# satima_clone.net
KiCad netlist of a schematic drawn in EasyEDA
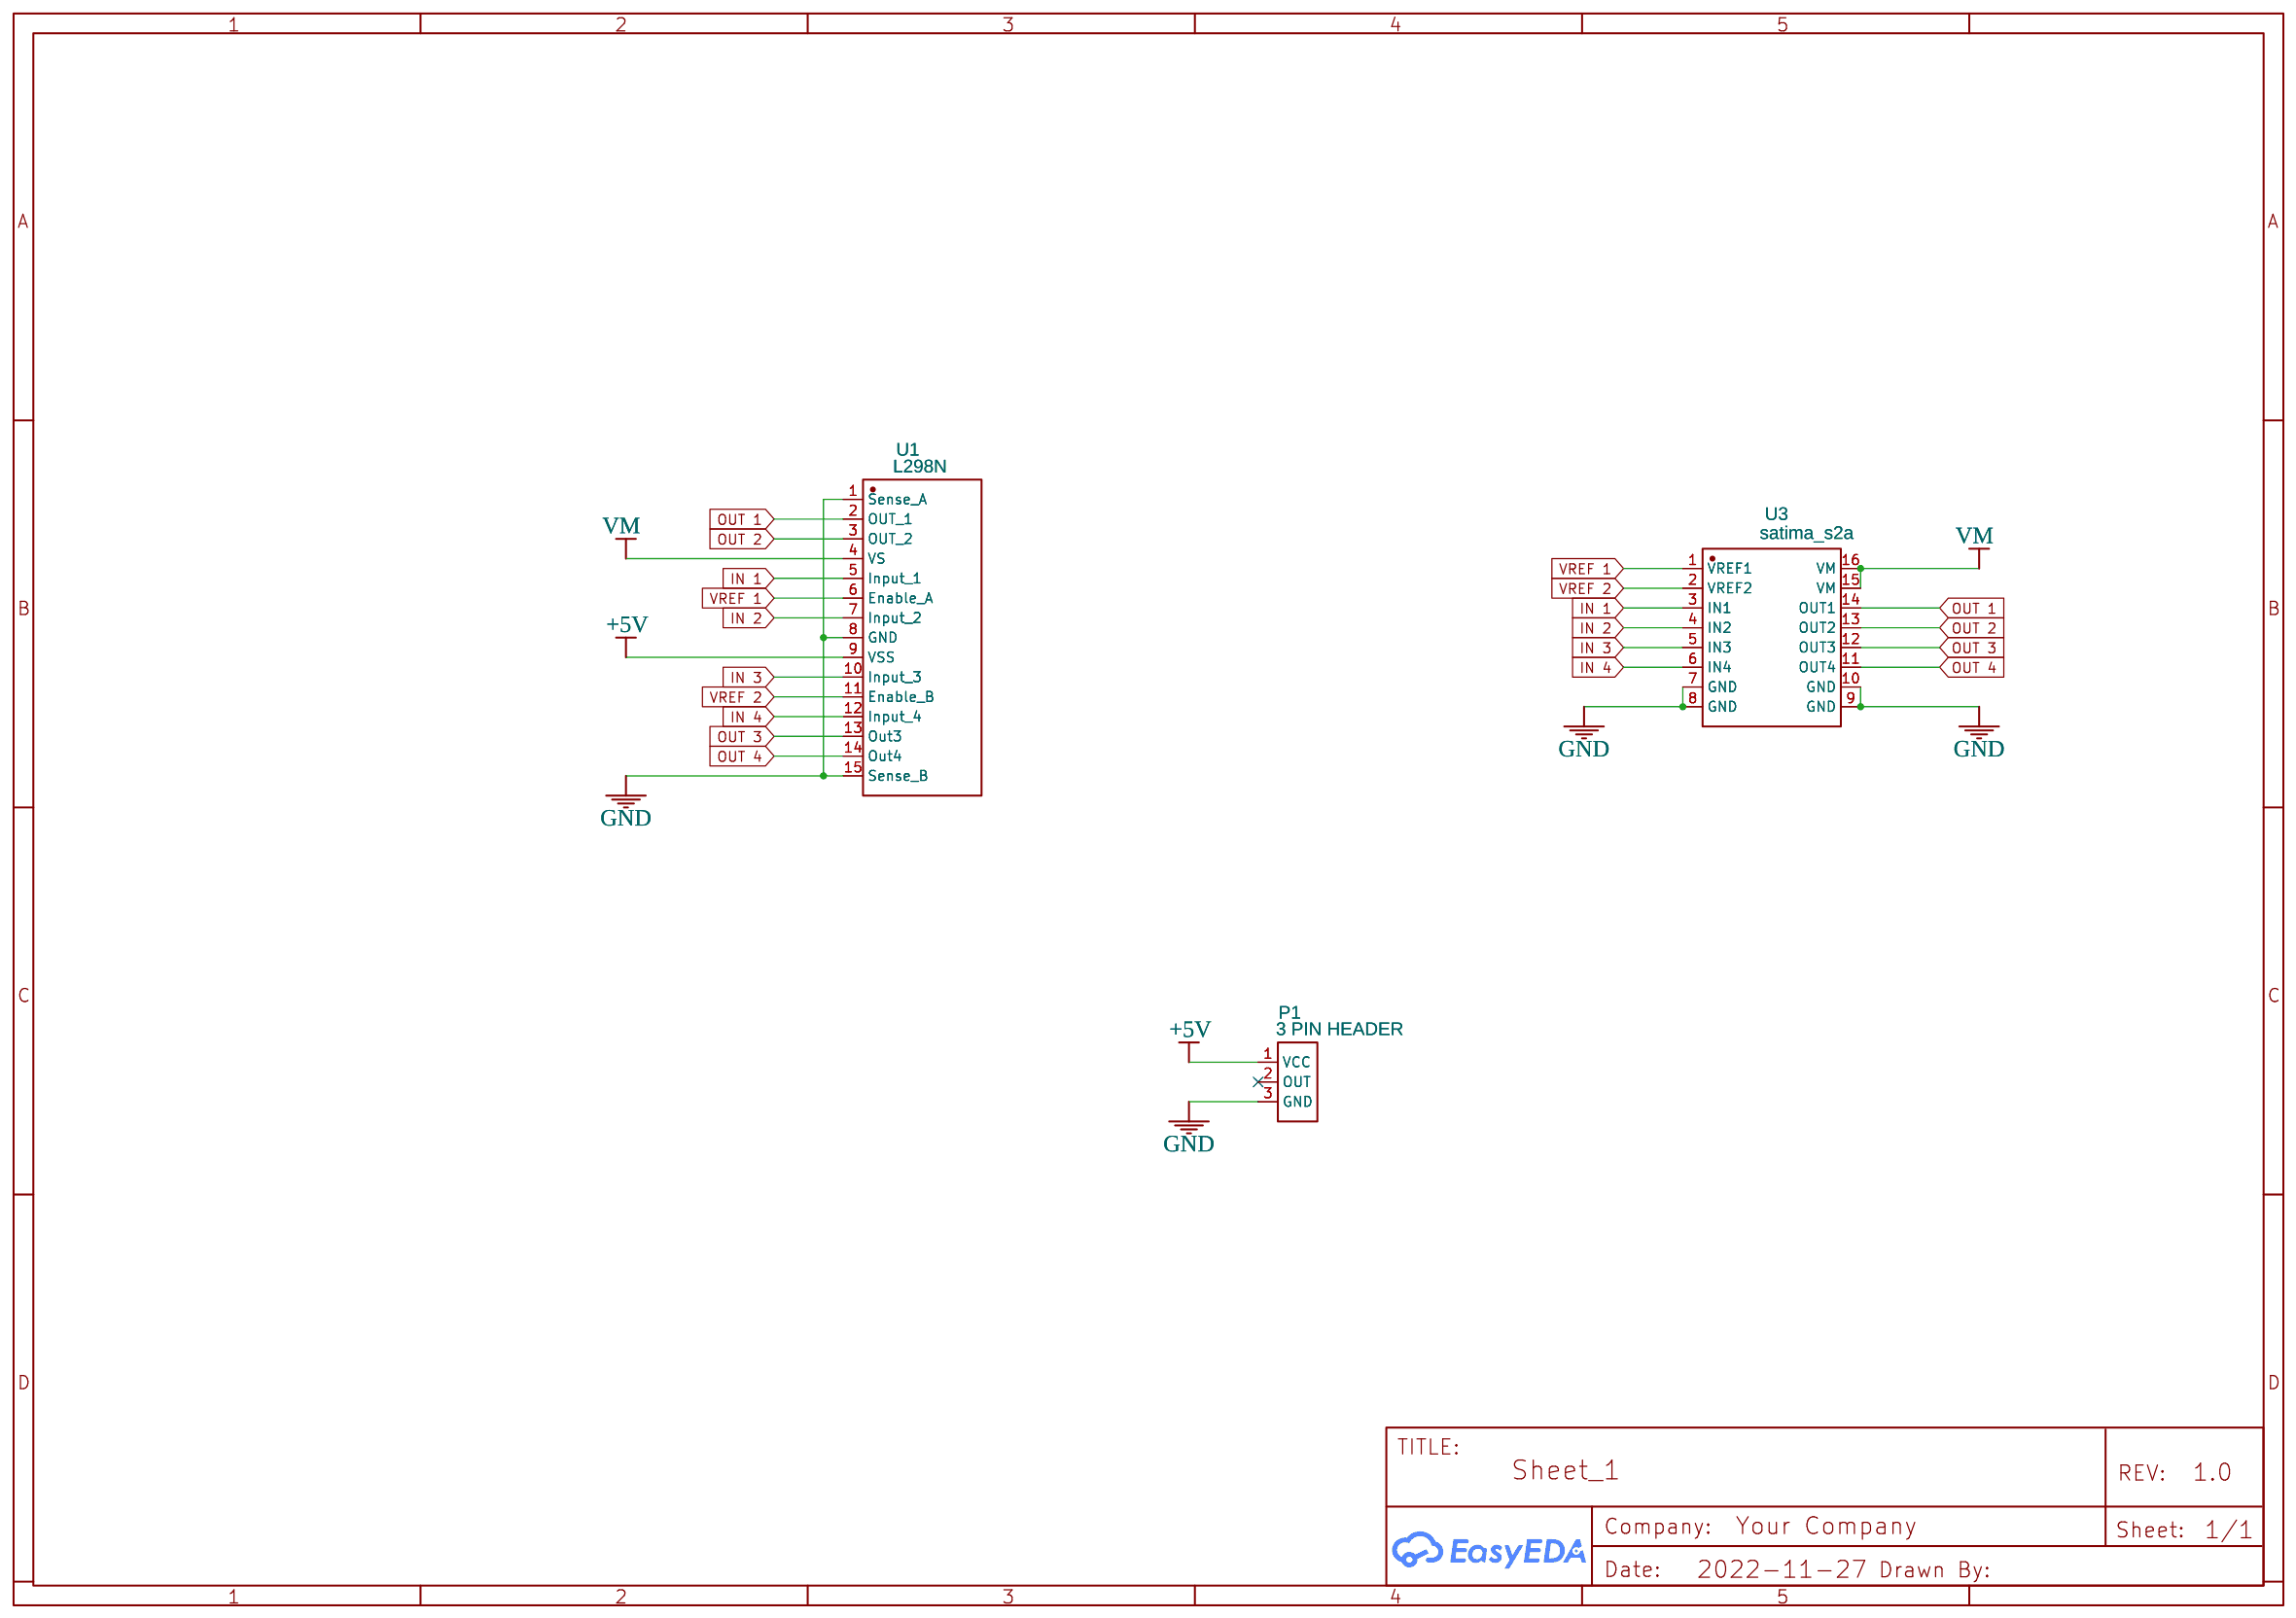
[diagram p0: schematic sheet]

(export (version "E")
  (design (tool "Eeschema 10.0.6"))
  (components
    (comp (ref "P1") (value "3 PIN HEADER") (libsource (lib "") (part "3 PIN HEADER")))
    (comp (ref "U1")
      (value "L298N")
      (fields (field (name "BOM_Supplier Part") "C434589"))
      (libsource (lib "") (part "L298N"))
    )
    (comp (ref "U3") (value "satima_s2a") (libsource (lib "") (part "satima_s2a")))
  )
  (nets
    (net (code "1") (name "+5V") (class "Default")
      (node (ref "P1") (pin "1") (pinfunction "VCC_1") (pintype "unspecified"))
      (node (ref "U1") (pin "9") (pinfunction "VSS_9") (pintype "unspecified"))
    )
    (net (code "2") (name "GND") (class "Default")
      (node (ref "P1") (pin "3") (pinfunction "GND_3") (pintype "unspecified"))
      (node (ref "U1") (pin "1") (pinfunction "Sense_A_1") (pintype "unspecified"))
      (node (ref "U1") (pin "15") (pinfunction "Sense_B_15") (pintype "unspecified"))
      (node (ref "U1") (pin "8") (pinfunction "GND_8") (pintype "unspecified"))
      (node (ref "U3") (pin "10") (pinfunction "GND_10") (pintype "unspecified"))
      (node (ref "U3") (pin "7") (pinfunction "GND_7") (pintype "unspecified"))
      (node (ref "U3") (pin "8") (pinfunction "GND_8") (pintype "unspecified"))
      (node (ref "U3") (pin "9") (pinfunction "GND_9") (pintype "unspecified"))
    )
    (net (code "3") (name "IN 1") (class "Default")
      (node (ref "U1") (pin "5") (pinfunction "Input_1_5") (pintype "unspecified"))
      (node (ref "U3") (pin "3") (pinfunction "IN1_3") (pintype "unspecified"))
    )
    (net (code "4") (name "IN 2") (class "Default")
      (node (ref "U1") (pin "7") (pinfunction "Input_2_7") (pintype "unspecified"))
      (node (ref "U3") (pin "4") (pinfunction "IN2_4") (pintype "unspecified"))
    )
    (net (code "5") (name "IN 3") (class "Default")
      (node (ref "U1") (pin "10") (pinfunction "Input_3_10") (pintype "unspecified"))
      (node (ref "U3") (pin "5") (pinfunction "IN3_5") (pintype "unspecified"))
    )
    (net (code "6") (name "IN 4") (class "Default")
      (node (ref "U1") (pin "12") (pinfunction "Input_4_12") (pintype "unspecified"))
      (node (ref "U3") (pin "6") (pinfunction "IN4_6") (pintype "unspecified"))
    )
    (net (code "7") (name "OUT 1") (class "Default")
      (node (ref "U1") (pin "2") (pinfunction "OUT_1_2") (pintype "unspecified"))
      (node (ref "U3") (pin "14") (pinfunction "OUT1_14") (pintype "unspecified"))
    )
    (net (code "8") (name "OUT 2") (class "Default")
      (node (ref "U1") (pin "3") (pinfunction "OUT_2_3") (pintype "unspecified"))
      (node (ref "U3") (pin "13") (pinfunction "OUT2_13") (pintype "unspecified"))
    )
    (net (code "9") (name "OUT 3") (class "Default")
      (node (ref "U1") (pin "13") (pinfunction "Out3_13") (pintype "unspecified"))
      (node (ref "U3") (pin "12") (pinfunction "OUT3_12") (pintype "unspecified"))
    )
    (net (code "10") (name "OUT 4") (class "Default")
      (node (ref "U1") (pin "14") (pinfunction "Out4_14") (pintype "unspecified"))
      (node (ref "U3") (pin "11") (pinfunction "OUT4_11") (pintype "unspecified"))
    )
    (net (code "11") (name "VM") (class "Default")
      (node (ref "U1") (pin "4") (pinfunction "VS_4") (pintype "unspecified"))
      (node (ref "U3") (pin "15") (pinfunction "VM_15") (pintype "unspecified"))
      (node (ref "U3") (pin "16") (pinfunction "VM_16") (pintype "unspecified"))
    )
    (net (code "12") (name "VREF 1") (class "Default")
      (node (ref "U1") (pin "6") (pinfunction "Enable_A_6") (pintype "unspecified"))
      (node (ref "U3") (pin "1") (pinfunction "VREF1_1") (pintype "unspecified"))
    )
    (net (code "13") (name "VREF 2") (class "Default")
      (node (ref "U1") (pin "11") (pinfunction "Enable_B_11") (pintype "unspecified"))
      (node (ref "U3") (pin "2") (pinfunction "VREF2_2") (pintype "unspecified"))
    )
    (net (code "14") (name "unconnected-(P1-OUT-Pad2)") (class "Default")
      (node (ref "P1") (pin "2") (pinfunction "OUT_2") (pintype "unspecified+no_connect"))
    )
  )
)
